# GateDriver.net
KiCad netlist of a schematic drawn in Altium Designer
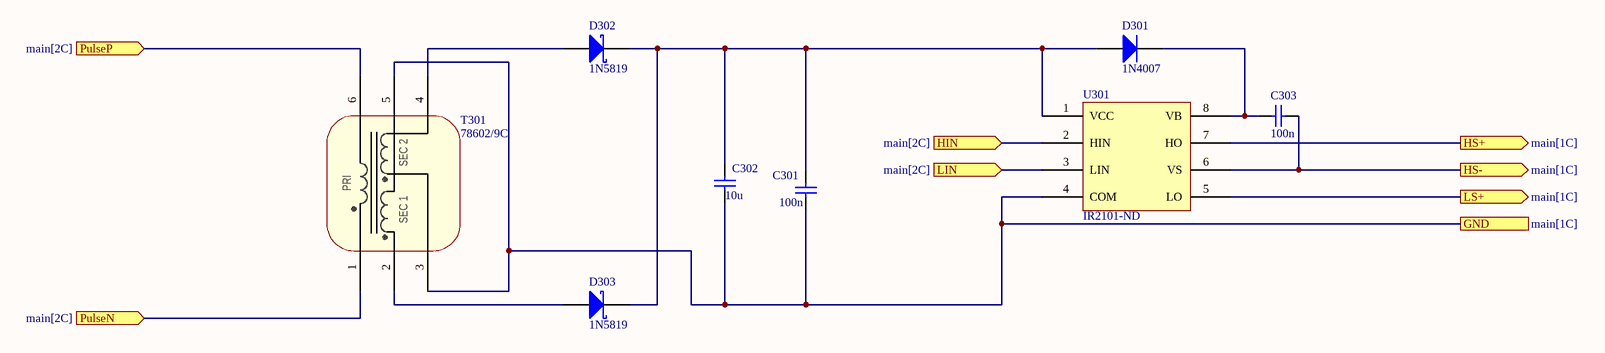
[diagram p0: GateDriver.SchDoc]

(export (version "E")
  (design (tool "Eeschema 10.0.6"))
  (components
    (comp (ref "C301")
      (value "100n")
      (footprint "CAP_1206")
      (description "Non Polarized Capacitor, SMD, 1206")
      (libsource (lib "Resistors and Capacitors") (part "CAPN 1206"))
    )
    (comp (ref "C302")
      (value "10u")
      (footprint "CAP_1206")
      (description "Non Polarized Capacitor, SMD, 1206")
      (libsource (lib "Resistors and Capacitors") (part "CAPN 1206"))
    )
    (comp (ref "C303")
      (value "100n")
      (footprint "RAD-0.2_AUT")
      (description "Non Polarized Capacitor, Multilayer Ceramic Dipped Radial, Pitch 200mil")
      (libsource (lib "Resistors and Capacitors") (part "CAPN RAD0.2"))
    )
    (comp (ref "D301")
      (value "1N4007")
      (footprint "DIODE0.4_AUT")
      (description "Diode, Standard, 1A, 1000v")
      (libsource (lib "Diodes") (part "1N4007"))
    )
    (comp (ref "D302")
      (value "1N5819")
      (footprint "DIODE0.4_AUT")
      (description "Schottky Diode, 1A,40v")
      (libsource (lib "Diodes") (part "1N5819"))
    )
    (comp (ref "D303")
      (value "1N5819")
      (footprint "DIODE0.4_AUT")
      (description "Schottky Diode, 1A,40v")
      (libsource (lib "Diodes") (part "1N5819"))
    )
    (comp (ref "T301")
      (value "78602/9C")
      (footprint "DIP6W_AUT")
      (description "Pulse transformer 1:1:1")
      (libsource (lib "Projects_2025") (part "78602/9C"))
    )
    (comp (ref "U301")
      (value "IR2101-ND")
      (footprint "DIP8-AUT")
      (description "Half-Bridge Gate Driver IC Non-Inverting 8-PDIP")
      (libsource (lib "Schematics") (part "IR2101-ND"))
    )
  )
  (nets
    (net (code "1") (name "/GND") (class "Default")
      (node (ref "C301") (pin "1") (pinfunction "1_1") (pintype "passive"))
      (node (ref "C302") (pin "1") (pinfunction "1_1") (pintype "passive"))
      (node (ref "T301") (pin "3") (pinfunction "Sec1_2_3") (pintype "power_in"))
      (node (ref "T301") (pin "5") (pinfunction "Sec1_2_5") (pintype "power_in"))
      (node (ref "U301") (pin "4") (pinfunction "COM_4") (pintype "passive"))
    )
    (net (code "2") (name "/HIN") (class "Default")
      (node (ref "U301") (pin "2") (pinfunction "HIN_2") (pintype "passive"))
    )
    (net (code "3") (name "/HS+") (class "Default")
      (node (ref "U301") (pin "7") (pinfunction "HO_7") (pintype "passive"))
    )
    (net (code "4") (name "/HS-") (class "Default")
      (node (ref "C303") (pin "2") (pinfunction "2_2") (pintype "passive"))
      (node (ref "U301") (pin "6") (pinfunction "VS_6") (pintype "passive"))
    )
    (net (code "5") (name "/LIN") (class "Default")
      (node (ref "U301") (pin "3") (pinfunction "LIN_3") (pintype "passive"))
    )
    (net (code "6") (name "/LS+") (class "Default")
      (node (ref "U301") (pin "5") (pinfunction "LO_5") (pintype "passive"))
    )
    (net (code "7") (name "/PulseN") (class "Default")
      (node (ref "T301") (pin "1") (pinfunction "Pri_1_1") (pintype "power_in"))
    )
    (net (code "8") (name "/PulseP") (class "Default")
      (node (ref "T301") (pin "6") (pinfunction "Pri2_6") (pintype "power_in"))
    )
    (net (code "9") (name "Net-(T301-Sec1_1)") (class "Default")
      (node (ref "D303") (pin "A") (pinfunction "A_A") (pintype "passive"))
      (node (ref "T301") (pin "2") (pinfunction "Sec1_1_2") (pintype "power_in"))
    )
    (net (code "10") (name "Net-(T301-Sec2_2)") (class "Default")
      (node (ref "D302") (pin "A") (pinfunction "A_A") (pintype "passive"))
      (node (ref "T301") (pin "4") (pinfunction "Sec2_2_4") (pintype "power_in"))
    )
    (net (code "11") (name "Net-(U301-VB)") (class "Default")
      (node (ref "C303") (pin "1") (pinfunction "1_1") (pintype "passive"))
      (node (ref "D301") (pin "K") (pinfunction "K_K") (pintype "passive"))
      (node (ref "U301") (pin "8") (pinfunction "VB_8") (pintype "passive"))
    )
    (net (code "12") (name "Net-(U301-VCC)") (class "Default")
      (node (ref "C301") (pin "2") (pinfunction "2_2") (pintype "passive"))
      (node (ref "C302") (pin "2") (pinfunction "2_2") (pintype "passive"))
      (node (ref "D301") (pin "A") (pinfunction "A_A") (pintype "passive"))
      (node (ref "D302") (pin "K") (pinfunction "K_K") (pintype "passive"))
      (node (ref "D303") (pin "K") (pinfunction "K_K") (pintype "passive"))
      (node (ref "U301") (pin "1") (pinfunction "VCC_1") (pintype "passive"))
    )
  )
)
